# Supply.net
KiCad netlist of a schematic drawn in Altium Designer
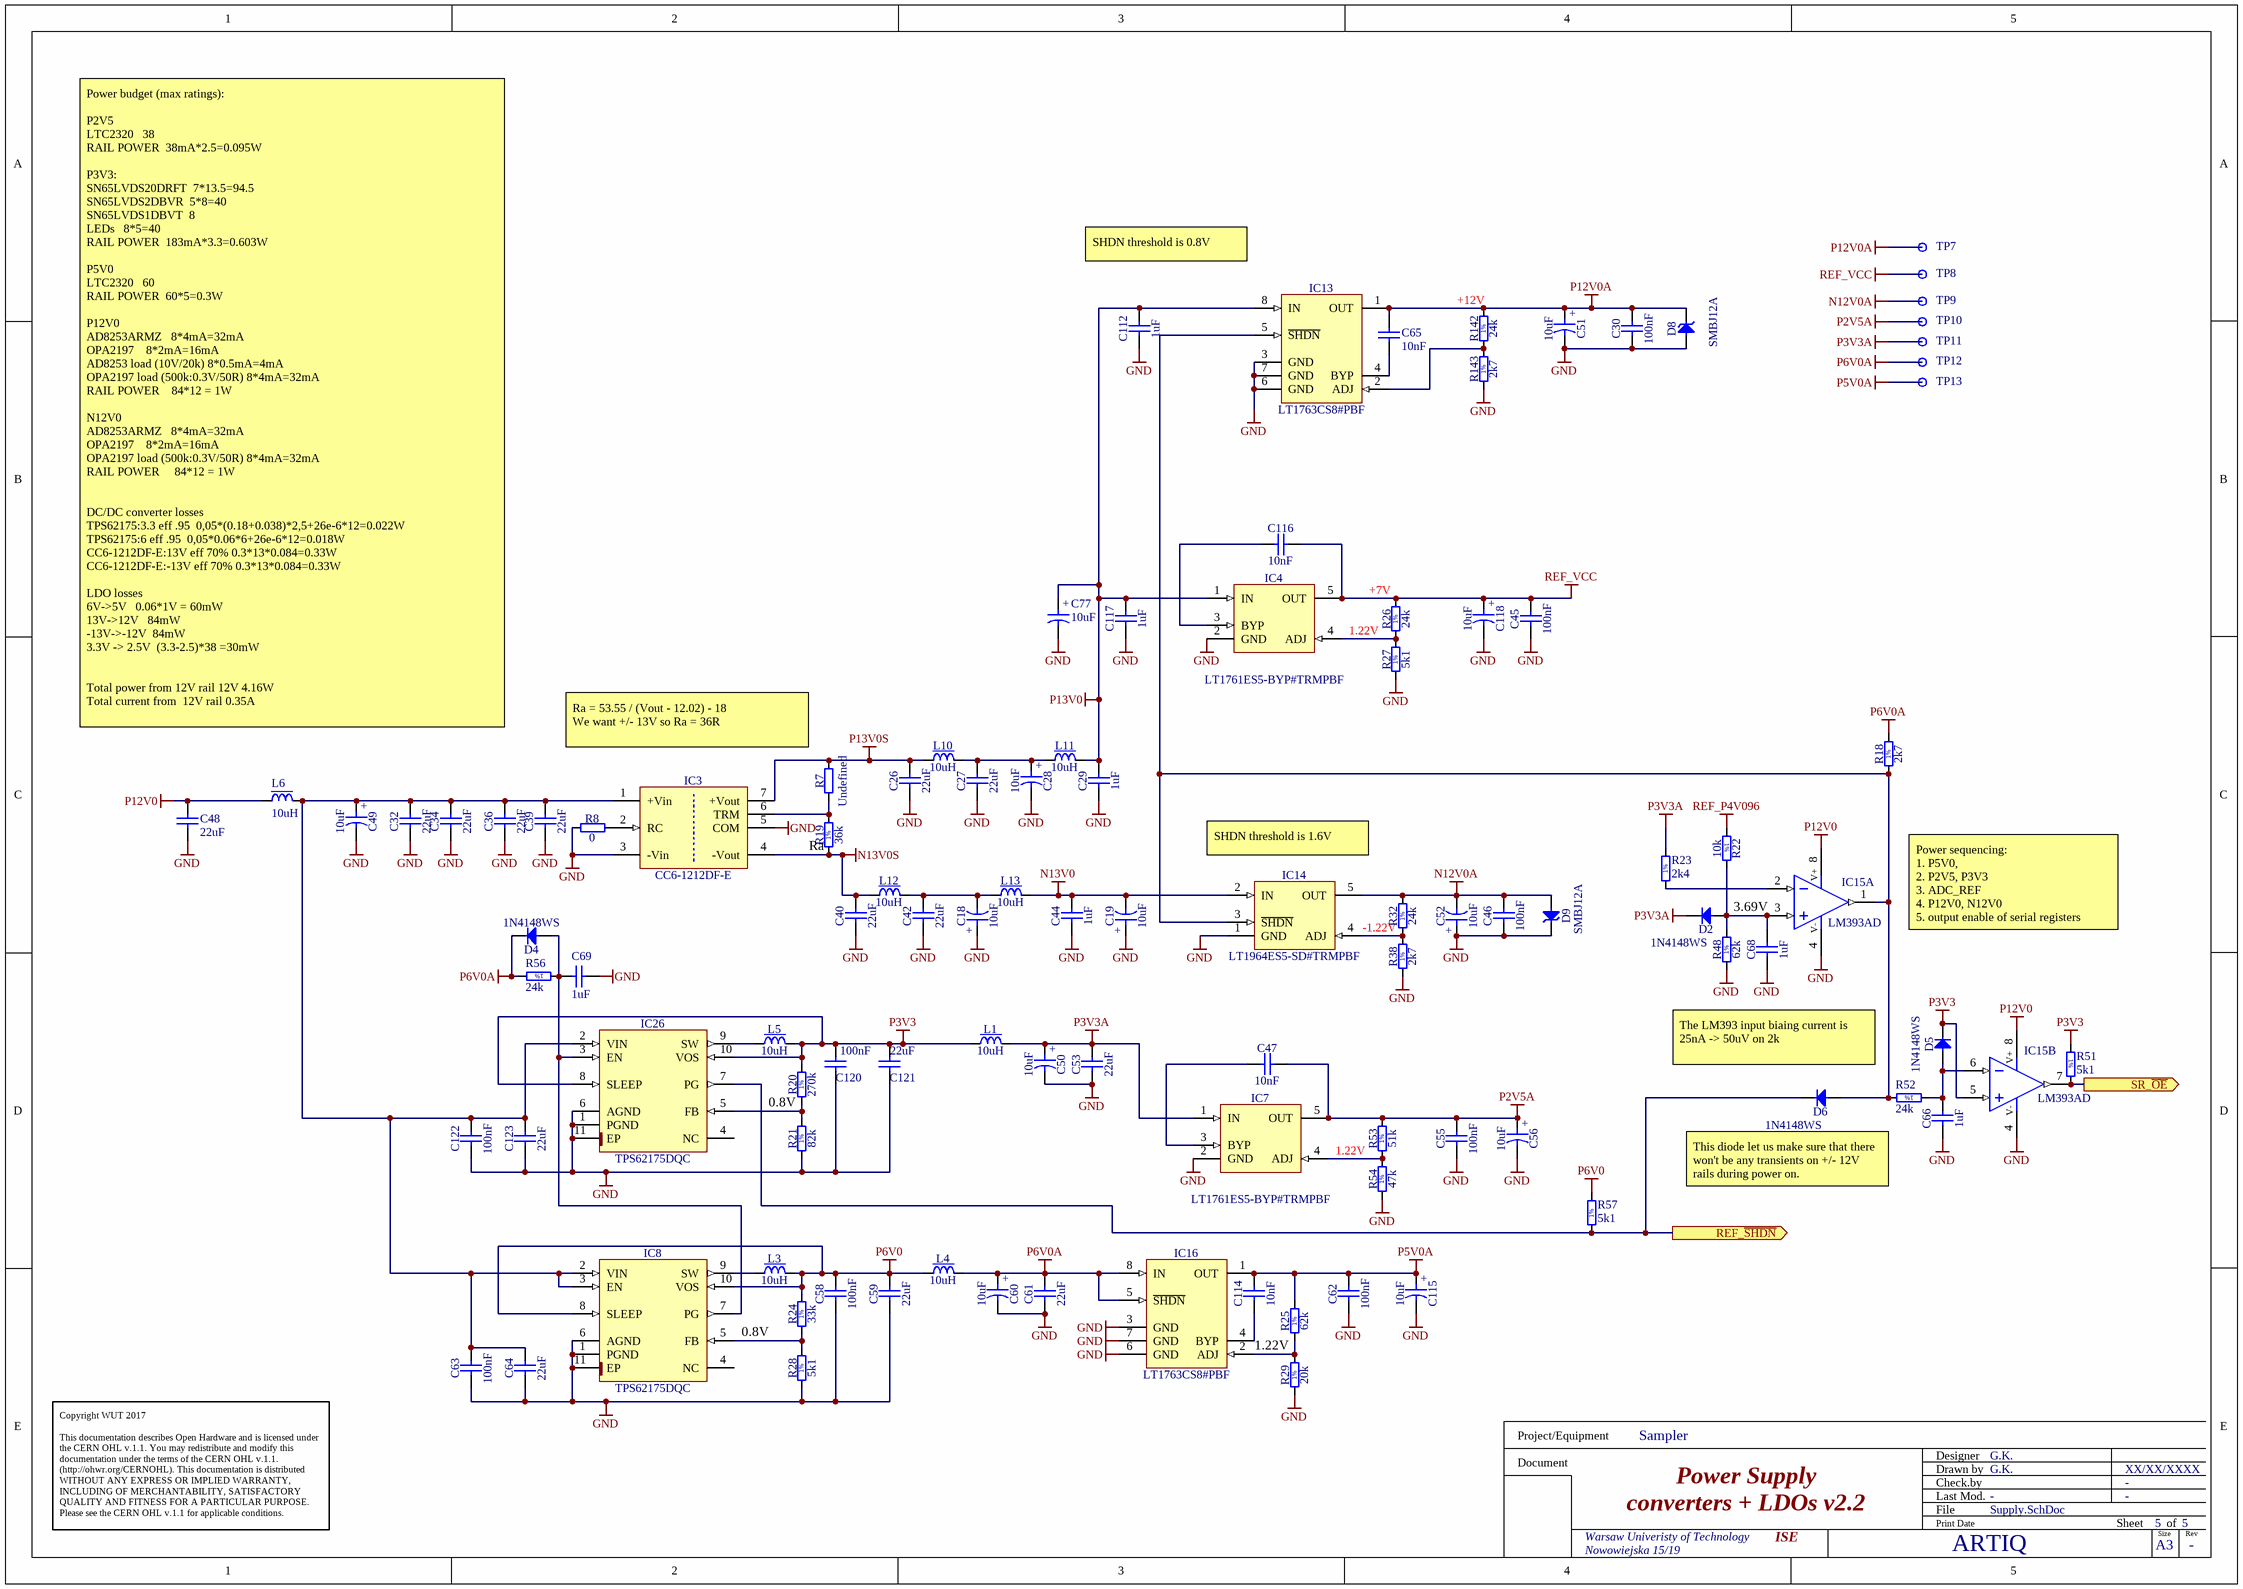
[diagram p0: Supply.SchDoc]

(export (version "E")
  (design (tool "Eeschema 10.0.6"))
  (components
    (comp (ref "C18")
      (value "10uF")
      (footprint "CAPMP3216X180N")
      (description "Polarised capacitor")
      (fields (field (name "PART NUMBER") "CTE3216-18_10UF_16V_20%_AVX_TCJ") (field (name "VOLTAGE") "16V"))
      (libsource (lib "Capacitors") (part "Capacitor - polarized"))
    )
    (comp (ref "C19")
      (value "10uF")
      (footprint "CAPMP3216X180N")
      (description "Polarised capacitor")
      (fields (field (name "PART NUMBER") "CTE3216-18_10UF_16V_20%_AVX_TCJ") (field (name "VOLTAGE") "16V"))
      (libsource (lib "Capacitors") (part "Capacitor - polarized"))
    )
    (comp (ref "C26")
      (value "22uF")
      (footprint "CAPC2012X135N")
      (description "Non-polarised capacitor")
      (fields (field (name "PART NUMBER") "CC0805_22UF_16V_10%_X5R") (field (name "VOLTAGE") "16V"))
      (libsource (lib "Capacitors") (part "Capacitor - non polarized"))
    )
    (comp (ref "C27")
      (value "22uF")
      (footprint "CAPC2012X135N")
      (description "Non-polarised capacitor")
      (fields (field (name "PART NUMBER") "CC0805_22UF_16V_10%_X5R") (field (name "VOLTAGE") "16V"))
      (libsource (lib "Capacitors") (part "Capacitor - non polarized"))
    )
    (comp (ref "C28")
      (value "10uF")
      (footprint "CAPMP3216X180N")
      (description "Polarised capacitor")
      (fields (field (name "PART NUMBER") "CTE3216-18_10UF_16V_20%_AVX_TCJ") (field (name "VOLTAGE") "16V"))
      (libsource (lib "Capacitors") (part "Capacitor - polarized"))
    )
    (comp (ref "C29")
      (value "1uF")
      (footprint "CAPC1608X87N")
      (description "Non-polarised capacitor")
      (fields (field (name "PART NUMBER") "CC0603_1UF_25V_10%_X7R") (field (name "VOLTAGE") "25V"))
      (libsource (lib "Capacitors") (part "Capacitor - non polarized"))
    )
    (comp (ref "C30")
      (value "100nF")
      (footprint "CAPC1005X55N")
      (description "Non-polarised capacitor")
      (fields (field (name "PART NUMBER") "CC0402_100NF_16V_10%_X5R") (field (name "VOLTAGE") "16V"))
      (libsource (lib "Capacitors") (part "Capacitor - non polarized"))
    )
    (comp (ref "C32")
      (value "22uF")
      (footprint "CAPC2012X135N")
      (description "Non-polarised capacitor")
      (fields (field (name "PART NUMBER") "CC0805_22UF_16V_10%_X5R") (field (name "VOLTAGE") "16V"))
      (libsource (lib "Capacitors") (part "Capacitor - non polarized"))
    )
    (comp (ref "C34")
      (value "22uF")
      (footprint "CAPC2012X135N")
      (description "Non-polarised capacitor")
      (fields (field (name "PART NUMBER") "CC0805_22UF_16V_10%_X5R") (field (name "VOLTAGE") "16V"))
      (libsource (lib "Capacitors") (part "Capacitor - non polarized"))
    )
    (comp (ref "C36")
      (value "22uF")
      (footprint "CAPC2012X135N")
      (description "Non-polarised capacitor")
      (fields (field (name "PART NUMBER") "CC0805_22UF_16V_10%_X5R") (field (name "VOLTAGE") "16V"))
      (libsource (lib "Capacitors") (part "Capacitor - non polarized"))
    )
    (comp (ref "C39")
      (value "22uF")
      (footprint "CAPC2012X135N")
      (description "Non-polarised capacitor")
      (fields (field (name "PART NUMBER") "CC0805_22UF_16V_10%_X5R") (field (name "VOLTAGE") "16V"))
      (libsource (lib "Capacitors") (part "Capacitor - non polarized"))
    )
    (comp (ref "C40")
      (value "22uF")
      (footprint "CAPC2012X135N")
      (description "Non-polarised capacitor")
      (fields (field (name "PART NUMBER") "CC0805_22UF_16V_10%_X5R") (field (name "VOLTAGE") "16V"))
      (libsource (lib "Capacitors") (part "Capacitor - non polarized"))
    )
    (comp (ref "C42")
      (value "22uF")
      (footprint "CAPC2012X135N")
      (description "Non-polarised capacitor")
      (fields (field (name "PART NUMBER") "CC0805_22UF_16V_10%_X5R") (field (name "VOLTAGE") "16V"))
      (libsource (lib "Capacitors") (part "Capacitor - non polarized"))
    )
    (comp (ref "C44")
      (value "1uF")
      (footprint "CAPC1608X87N")
      (description "Non-polarised capacitor")
      (fields (field (name "PART NUMBER") "CC0603_1UF_25V_10%_X7R") (field (name "VOLTAGE") "25V"))
      (libsource (lib "Capacitors") (part "Capacitor - non polarized"))
    )
    (comp (ref "C45")
      (value "100nF")
      (footprint "CAPC1005X55N")
      (description "Non-polarised capacitor")
      (fields (field (name "PART NUMBER") "CC0402_100NF_16V_10%_X5R") (field (name "VOLTAGE") "16V"))
      (libsource (lib "Capacitors") (part "Capacitor - non polarized"))
    )
    (comp (ref "C46")
      (value "100nF")
      (footprint "CAPC1005X55N")
      (description "Non-polarised capacitor")
      (fields (field (name "PART NUMBER") "CC0402_100NF_16V_10%_X5R") (field (name "VOLTAGE") "16V"))
      (libsource (lib "Capacitors") (part "Capacitor - non polarized"))
    )
    (comp (ref "C47")
      (value "10nF")
      (footprint "CAPC1608X87N")
      (description "Non-polarised capacitor")
      (fields (field (name "PART NUMBER") "CC0603_10NF_50V_10%_X7R") (field (name "VOLTAGE") "50V"))
      (libsource (lib "Capacitors") (part "Capacitor - non polarized"))
    )
    (comp (ref "C48")
      (value "22uF")
      (footprint "CAPC2012X135N")
      (description "Non-polarised capacitor")
      (fields (field (name "PART NUMBER") "CC0805_22UF_16V_10%_X5R") (field (name "VOLTAGE") "16V"))
      (libsource (lib "Capacitors") (part "Capacitor - non polarized"))
    )
    (comp (ref "C49")
      (value "10uF")
      (footprint "CAPMP3216X180N")
      (description "Polarised capacitor")
      (fields (field (name "PART NUMBER") "CTE3216-18_10UF_16V_20%_AVX_TCJ") (field (name "VOLTAGE") "16V"))
      (libsource (lib "Capacitors") (part "Capacitor - polarized"))
    )
    (comp (ref "C50")
      (value "10uF")
      (footprint "CAPMP3216X180N")
      (description "Polarised capacitor")
      (fields (field (name "PART NUMBER") "CTE3216-18_10UF_16V_20%_AVX_TCJ") (field (name "VOLTAGE") "16V"))
      (libsource (lib "Capacitors") (part "Capacitor - polarized"))
    )
    (comp (ref "C51")
      (value "10uF")
      (footprint "CAPMP3216X180N")
      (description "Polarised capacitor")
      (fields (field (name "PART NUMBER") "CTE3216-18_10UF_16V_20%_AVX_TCJ") (field (name "VOLTAGE") "16V"))
      (libsource (lib "Capacitors") (part "Capacitor - polarized"))
    )
    (comp (ref "C52")
      (value "10uF")
      (footprint "CAPMP3216X180N")
      (description "Polarised capacitor")
      (fields (field (name "PART NUMBER") "CTE3216-18_10UF_16V_20%_AVX_TCJ") (field (name "VOLTAGE") "16V"))
      (libsource (lib "Capacitors") (part "Capacitor - polarized"))
    )
    (comp (ref "C53")
      (value "22uF")
      (footprint "CAPC2012X135N")
      (description "Non-polarised capacitor")
      (fields (field (name "PART NUMBER") "CC0805_22UF_16V_10%_X5R") (field (name "VOLTAGE") "16V"))
      (libsource (lib "Capacitors") (part "Capacitor - non polarized"))
    )
    (comp (ref "C55")
      (value "100nF")
      (footprint "CAPC1005X55N")
      (description "Non-polarised capacitor")
      (fields (field (name "PART NUMBER") "CC0402_100NF_16V_10%_X5R") (field (name "VOLTAGE") "16V"))
      (libsource (lib "Capacitors") (part "Capacitor - non polarized"))
    )
    (comp (ref "C56")
      (value "10uF")
      (footprint "CAPMP3216X180N")
      (description "Polarised capacitor")
      (fields (field (name "PART NUMBER") "CTE3216-18_10UF_16V_20%_AVX_TCJ") (field (name "VOLTAGE") "16V"))
      (libsource (lib "Capacitors") (part "Capacitor - polarized"))
    )
    (comp (ref "C58")
      (value "100nF")
      (footprint "CAPC1005X55N")
      (description "Non-polarised capacitor")
      (fields (field (name "PART NUMBER") "CC0402_100NF_16V_10%_X5R") (field (name "VOLTAGE") "16V"))
      (libsource (lib "Capacitors") (part "Capacitor - non polarized"))
    )
    (comp (ref "C59")
      (value "22uF")
      (footprint "CAPC2012X135N")
      (description "Non-polarised capacitor")
      (fields (field (name "PART NUMBER") "CC0805_22UF_16V_10%_X5R") (field (name "VOLTAGE") "16V"))
      (libsource (lib "Capacitors") (part "Capacitor - non polarized"))
    )
    (comp (ref "C60")
      (value "10uF")
      (footprint "CAPMP3216X180N")
      (description "Polarised capacitor")
      (fields (field (name "PART NUMBER") "CTE3216-18_10UF_16V_20%_AVX_TCJ") (field (name "VOLTAGE") "16V"))
      (libsource (lib "Capacitors") (part "Capacitor - polarized"))
    )
    (comp (ref "C61")
      (value "22uF")
      (footprint "CAPC2012X135N")
      (description "Non-polarised capacitor")
      (fields (field (name "PART NUMBER") "CC0805_22UF_16V_10%_X5R") (field (name "VOLTAGE") "16V"))
      (libsource (lib "Capacitors") (part "Capacitor - non polarized"))
    )
    (comp (ref "C62")
      (value "100nF")
      (footprint "CAPC1005X55N")
      (description "Non-polarised capacitor")
      (fields (field (name "PART NUMBER") "CC0402_100NF_16V_10%_X5R") (field (name "VOLTAGE") "16V"))
      (libsource (lib "Capacitors") (part "Capacitor - non polarized"))
    )
    (comp (ref "C63")
      (value "100nF")
      (footprint "CAPC1005X55N")
      (description "Non-polarised capacitor")
      (fields (field (name "PART NUMBER") "CC0402_100NF_16V_10%_X5R") (field (name "VOLTAGE") "16V"))
      (libsource (lib "Capacitors") (part "Capacitor - non polarized"))
    )
    (comp (ref "C64")
      (value "22uF")
      (footprint "CAPC2012X135N")
      (description "Non-polarised capacitor")
      (fields (field (name "PART NUMBER") "CC0805_22UF_16V_10%_X5R") (field (name "VOLTAGE") "16V"))
      (libsource (lib "Capacitors") (part "Capacitor - non polarized"))
    )
    (comp (ref "C65")
      (value "10nF")
      (footprint "CAPC1608X87N")
      (description "Non-polarised capacitor")
      (fields (field (name "PART NUMBER") "CC0603_10NF_50V_10%_X7R") (field (name "VOLTAGE") "50V"))
      (libsource (lib "Capacitors") (part "Capacitor - non polarized"))
    )
    (comp (ref "C66")
      (value "1uF")
      (footprint "CAPC1608X87N")
      (description "Non-polarised capacitor")
      (fields (field (name "PART NUMBER") "CC0603_1UF_25V_10%_X7R") (field (name "VOLTAGE") "25V"))
      (libsource (lib "Capacitors") (part "Capacitor - non polarized"))
    )
    (comp (ref "C68")
      (value "1uF")
      (footprint "CAPC1608X87N")
      (description "Non-polarised capacitor")
      (fields (field (name "PART NUMBER") "CC0603_1UF_25V_10%_X7R") (field (name "VOLTAGE") "25V"))
      (libsource (lib "Capacitors") (part "Capacitor - non polarized"))
    )
    (comp (ref "C69")
      (value "1uF")
      (footprint "CAPC1608X87N")
      (description "Non-polarised capacitor")
      (fields (field (name "PART NUMBER") "CC0603_1UF_25V_10%_X7R") (field (name "VOLTAGE") "25V"))
      (libsource (lib "Capacitors") (part "Capacitor - non polarized"))
    )
    (comp (ref "C77")
      (value "10uF")
      (footprint "CAPMP3216X180N")
      (description "Polarised capacitor")
      (fields (field (name "PART NUMBER") "CTE3216-18_10UF_16V_20%_AVX_TCJ") (field (name "VOLTAGE") "16V"))
      (libsource (lib "Capacitors") (part "Capacitor - polarized"))
    )
    (comp (ref "C112")
      (value "1uF")
      (footprint "CAPC1608X87N")
      (description "Non-polarised capacitor")
      (fields (field (name "PART NUMBER") "CC0603_1UF_25V_10%_X7R") (field (name "VOLTAGE") "25V"))
      (libsource (lib "Capacitors") (part "Capacitor - non polarized"))
    )
    (comp (ref "C114")
      (value "10nF")
      (footprint "CAPC1608X87N")
      (description "Non-polarised capacitor")
      (fields (field (name "PART NUMBER") "CC0603_10NF_50V_10%_X7R") (field (name "VOLTAGE") "50V"))
      (libsource (lib "Capacitors") (part "Capacitor - non polarized"))
    )
    (comp (ref "C115")
      (value "10uF")
      (footprint "CAPMP3216X180N")
      (description "Polarised capacitor")
      (fields (field (name "PART NUMBER") "CTE3216-18_10UF_16V_20%_AVX_TCJ") (field (name "VOLTAGE") "16V"))
      (libsource (lib "Capacitors") (part "Capacitor - polarized"))
    )
    (comp (ref "C116")
      (value "10nF")
      (footprint "CAPC1608X87N")
      (description "Non-polarised capacitor")
      (fields (field (name "PART NUMBER") "CC0603_10NF_50V_10%_X7R") (field (name "VOLTAGE") "50V"))
      (libsource (lib "Capacitors") (part "Capacitor - non polarized"))
    )
    (comp (ref "C117")
      (value "1uF")
      (footprint "CAPC1608X87N")
      (description "Non-polarised capacitor")
      (fields (field (name "PART NUMBER") "CC0603_1UF_25V_10%_X7R") (field (name "VOLTAGE") "25V"))
      (libsource (lib "Capacitors") (part "Capacitor - non polarized"))
    )
    (comp (ref "C118")
      (value "10uF")
      (footprint "CAPMP3216X180N")
      (description "Polarised capacitor")
      (fields (field (name "PART NUMBER") "CTE3216-18_10UF_16V_20%_AVX_TCJ") (field (name "VOLTAGE") "16V"))
      (libsource (lib "Capacitors") (part "Capacitor - polarized"))
    )
    (comp (ref "C120")
      (value "100nF")
      (footprint "CAPC1005X55N")
      (description "Non-polarised capacitor")
      (fields (field (name "PART NUMBER") "CC0402_100NF_16V_10%_X5R") (field (name "VOLTAGE") "16V"))
      (libsource (lib "Capacitors") (part "Capacitor - non polarized"))
    )
    (comp (ref "C121")
      (value "22uF")
      (footprint "CAPC2012X135N")
      (description "Non-polarised capacitor")
      (fields (field (name "PART NUMBER") "CC0805_22UF_16V_10%_X5R") (field (name "VOLTAGE") "16V"))
      (libsource (lib "Capacitors") (part "Capacitor - non polarized"))
    )
    (comp (ref "C122")
      (value "100nF")
      (footprint "CAPC1005X55N")
      (description "Non-polarised capacitor")
      (fields (field (name "PART NUMBER") "CC0402_100NF_16V_10%_X5R") (field (name "VOLTAGE") "16V"))
      (libsource (lib "Capacitors") (part "Capacitor - non polarized"))
    )
    (comp (ref "C123")
      (value "22uF")
      (footprint "CAPC2012X135N")
      (description "Non-polarised capacitor")
      (fields (field (name "PART NUMBER") "CC0805_22UF_16V_10%_X5R") (field (name "VOLTAGE") "16V"))
      (libsource (lib "Capacitors") (part "Capacitor - non polarized"))
    )
    (comp (ref "D2")
      (value "1N4148WS")
      (footprint "SODFL2512X100N")
      (description "Diode")
      (fields (field (name "VOLTAGE") "75V") (field (name "POWER") "150mA"))
      (libsource (lib "ICs And Semiconductors") (part "Diode"))
    )
    (comp (ref "D4")
      (value "1N4148WS")
      (footprint "SODFL2512X100N")
      (description "Diode")
      (fields (field (name "VOLTAGE") "75V") (field (name "POWER") "150mA"))
      (libsource (lib "ICs And Semiconductors") (part "Diode"))
    )
    (comp (ref "D5")
      (value "1N4148WS")
      (footprint "SODFL2512X100N")
      (description "Diode")
      (fields (field (name "VOLTAGE") "75V") (field (name "POWER") "150mA"))
      (libsource (lib "ICs And Semiconductors") (part "Diode"))
    )
    (comp (ref "D6")
      (value "1N4148WS")
      (footprint "SODFL2512X100N")
      (description "Diode")
      (fields (field (name "VOLTAGE") "75V") (field (name "POWER") "150mA"))
      (libsource (lib "ICs And Semiconductors") (part "Diode"))
    )
    (comp (ref "D8")
      (value "SMBJ12A")
      (footprint "DIOM5336X265N")
      (description "Zener Diode")
      (fields (field (name "VOLTAGE") "12V") (field (name "POWER") "600W"))
      (libsource (lib "ICs And Semiconductors") (part "Diode Zener"))
    )
    (comp (ref "D9")
      (value "SMBJ12A")
      (footprint "DIOM5336X265N")
      (description "Zener Diode")
      (fields (field (name "VOLTAGE") "12V") (field (name "POWER") "600W"))
      (libsource (lib "ICs And Semiconductors") (part "Diode Zener"))
    )
    (comp (ref "IC3")
      (value "CC6-1212DF-E")
      (footprint "CC6-1212DF-E")
      (description "CONV DC/DC 6W DUAL 12V +-12V PCB")
      (fields (field (name "MANUFACTURER") "TDK-Lambda Americas Inc."))
      (libsource (lib "LIBRARY_SCH") (part "DC/DC_CC6-1212DF-E"))
    )
    (comp (ref "IC4")
      (value "LT1761ES5-BYP#TRMPBF")
      (footprint "SOT95P280X100-5N")
      (description "100mA, Low Noise, LDO Micropower Adjustable Regulator in SOT-23")
      (fields (field (name "MANUFACTURER") "LINEAR TECHNOLOGY"))
      (libsource (lib "ICs And Semiconductors") (part "LT1761-BYP"))
    )
    (comp (ref "IC7")
      (value "LT1761ES5-BYP#TRMPBF")
      (footprint "SOT95P280X100-5N")
      (description "100mA, Low Noise, LDO Micropower Adjustable Regulator in SOT-23")
      (fields (field (name "MANUFACTURER") "LINEAR TECHNOLOGY"))
      (libsource (lib "ICs And Semiconductors") (part "LT1761-BYP"))
    )
    (comp (ref "IC8")
      (value "TPS62175DQC")
      (footprint "SON50P200X300X80-11N-R94X250")
      (description "4.75-28VDC to 1-6VDC, 500mA Step-Down Converter With Sleep Mode")
      (fields (field (name "MANUFACTURER") "TEXAS INSTRUMENTS"))
      (libsource (lib "ICs And Semiconductors") (part "TPS62175"))
    )
    (comp (ref "IC13")
      (value "LT1763CS8#PBF")
      (footprint "SOIC127P600X175-8N")
      (description "1.22V to 20V 500mA, Low Noise, LDO Adjustable Micropower Regulator")
      (fields (field (name "MANUFACTURER") "LINEAR TECHNOLOGY"))
      (libsource (lib "ICs And Semiconductors") (part "LT1763xS8"))
    )
    (comp (ref "IC14")
      (value "LT1964ES5-SD#TRMPBF")
      (footprint "SOT95P280X100-5N")
      (description "200mA, Low Noise, Low Dropout Negative Micropower Regulator")
      (fields (field (name "MANUFACTURER") "LINEAR TECHNOLOGY"))
      (libsource (lib "ICs And Semiconductors") (part "LT1964-SD"))
    )
    (comp (ref "IC15")
      (value "LM393AD")
      (footprint "SOIC127P600X175-8N")
      (description "Dual Operational Amplifier")
      (fields (field (name "MANUFACTURER") "TEXAS INSTRUMENTS"))
      (libsource (lib "ICs And Semiconductors") (part "Operational Amplifier x2 Type1"))
    )
    (comp (ref "IC16")
      (value "LT1763CS8#PBF")
      (footprint "SOIC127P600X175-8N")
      (description "1.22V to 20V 500mA, Low Noise, LDO Adjustable Micropower Regulator")
      (fields (field (name "MANUFACTURER") "LINEAR TECHNOLOGY"))
      (libsource (lib "ICs And Semiconductors") (part "LT1763xS8"))
    )
    (comp (ref "IC26")
      (value "TPS62175DQC")
      (footprint "SON50P200X300X80-11N-R94X250")
      (description "4.75-28VDC to 1-6VDC, 500mA Step-Down Converter With Sleep Mode")
      (fields (field (name "MANUFACTURER") "TEXAS INSTRUMENTS"))
      (libsource (lib "ICs And Semiconductors") (part "TPS62175"))
    )
    (comp (ref "L1")
      (value "10uH")
      (footprint "IND_MURATA-PS_8400")
      (description "Inductor With Core")
      (fields (field (name "PART NUMBER") "IND_10UH_10%_MURATA-PS_8400") (field (name "POWER") "950mA"))
      (libsource (lib "Inductors & Transformers") (part "Inductor With Magnetic core"))
    )
    (comp (ref "L3")
      (value "10uH")
      (footprint "IND_MURATA-PS_8400")
      (description "Inductor With Core")
      (fields (field (name "PART NUMBER") "IND_10UH_10%_MURATA-PS_8400") (field (name "POWER") "950mA"))
      (libsource (lib "Inductors & Transformers") (part "Inductor With Magnetic core"))
    )
    (comp (ref "L4")
      (value "10uH")
      (footprint "IND_MURATA-PS_8400")
      (description "Inductor With Core")
      (fields (field (name "PART NUMBER") "IND_10UH_10%_MURATA-PS_8400") (field (name "POWER") "950mA"))
      (libsource (lib "Inductors & Transformers") (part "Inductor With Magnetic core"))
    )
    (comp (ref "L5")
      (value "10uH")
      (footprint "IND_MURATA-PS_8400")
      (description "Inductor With Core")
      (fields (field (name "PART NUMBER") "IND_10UH_10%_MURATA-PS_8400") (field (name "POWER") "950mA"))
      (libsource (lib "Inductors & Transformers") (part "Inductor With Magnetic core"))
    )
    (comp (ref "L6")
      (value "10uH")
      (footprint "IND_MURATA-PS_8400")
      (description "Inductor With Core")
      (fields (field (name "PART NUMBER") "IND_10UH_10%_MURATA-PS_8400") (field (name "POWER") "950mA"))
      (libsource (lib "Inductors & Transformers") (part "Inductor With Magnetic core"))
    )
    (comp (ref "L10")
      (value "10uH")
      (footprint "IND_MURATA-PS_8400")
      (description "Inductor With Core")
      (fields (field (name "PART NUMBER") "IND_10UH_10%_MURATA-PS_8400") (field (name "POWER") "950mA"))
      (libsource (lib "Inductors & Transformers") (part "Inductor With Magnetic core"))
    )
    (comp (ref "L11")
      (value "10uH")
      (footprint "IND_MURATA-PS_8400")
      (description "Inductor With Core")
      (fields (field (name "PART NUMBER") "IND_10UH_10%_MURATA-PS_8400") (field (name "POWER") "950mA"))
      (libsource (lib "Inductors & Transformers") (part "Inductor With Magnetic core"))
    )
    (comp (ref "L12")
      (value "10uH")
      (footprint "IND_MURATA-PS_8400")
      (description "Inductor With Core")
      (fields (field (name "PART NUMBER") "IND_10UH_10%_MURATA-PS_8400") (field (name "POWER") "950mA"))
      (libsource (lib "Inductors & Transformers") (part "Inductor With Magnetic core"))
    )
    (comp (ref "L13")
      (value "10uH")
      (footprint "IND_MURATA-PS_8400")
      (description "Inductor With Core")
      (fields (field (name "PART NUMBER") "IND_10UH_10%_MURATA-PS_8400") (field (name "POWER") "950mA"))
      (libsource (lib "Inductors & Transformers") (part "Inductor With Magnetic core"))
    )
    (comp (ref "R7")
      (value "Undefined")
      (footprint "RESC1608X55N")
      (description "Resistor")
      (fields (field (name "PART NUMBER") "R0603_NO-VALUE"))
      (libsource (lib "Resistors") (part "Resistor"))
    )
    (comp (ref "R8")
      (value "0")
      (footprint "RESC1005X40N")
      (description "Resistor")
      (fields (field (name "PART NUMBER") "R0402_0R_JUMPER") (field (name "MANUFACTURER") "GENERIC"))
      (libsource (lib "Resistors") (part "Resistor"))
    )
    (comp (ref "R18")
      (value "2k7")
      (footprint "RESC1608X55N")
      (description "Resistor - 1%")
      (fields (field (name "PART NUMBER") "R0603_2K7_1%_0.1W_100PPM") (field (name "POWER") "0.1W"))
      (libsource (lib "Resistors") (part "Resistor - 1%"))
    )
    (comp (ref "R19")
      (value "36k")
      (footprint "RESC1608X55N")
      (description "Resistor - 1%")
      (fields (field (name "PART NUMBER") "R0603_36K_1%_0.1W_100PPM") (field (name "POWER") "0.1W"))
      (libsource (lib "Resistors") (part "Resistor - 1%"))
    )
    (comp (ref "R20")
      (value "270k")
      (footprint "RESC1608X55N")
      (description "Resistor - 1%")
      (fields (field (name "PART NUMBER") "R0603_270K_1%_0.1W_100PPM") (field (name "POWER") "0.1W"))
      (libsource (lib "Resistors") (part "Resistor - 1%"))
    )
    (comp (ref "R21")
      (value "82k")
      (footprint "RESC1608X55N")
      (description "Resistor - 1%")
      (fields (field (name "PART NUMBER") "R0603_82K_1%_0.1W_100PPM") (field (name "POWER") "0.1W"))
      (libsource (lib "Resistors") (part "Resistor - 1%"))
    )
    (comp (ref "R22")
      (value "10k")
      (footprint "RESC1005X40N")
      (description "Resistor - 1%")
      (fields (field (name "PART NUMBER") "R0402_10K_1%_0.0625W_100PPM") (field (name "POWER") "0.0625W"))
      (libsource (lib "Resistors") (part "Resistor - 1%"))
    )
    (comp (ref "R23")
      (value "2k4")
      (footprint "RESC1005X40N")
      (description "Resistor - 1%")
      (fields (field (name "PART NUMBER") "R0402_2K4_1%_0.0625W_100PPM") (field (name "POWER") "0.0625W"))
      (libsource (lib "Resistors") (part "Resistor - 1%"))
    )
    (comp (ref "R24")
      (value "33k")
      (footprint "RESC1005X40N")
      (description "Resistor - 1%")
      (fields (field (name "PART NUMBER") "R0402_33K_1%_0.0625W_100PPM") (field (name "POWER") "0.0625W"))
      (libsource (lib "Resistors") (part "Resistor - 1%"))
    )
    (comp (ref "R25")
      (value "62k")
      (footprint "RESC1005X40N")
      (description "Resistor - 1%")
      (fields (field (name "PART NUMBER") "R0402_62K_1%_0.0625W_100PPM") (field (name "POWER") "0.0625W"))
      (libsource (lib "Resistors") (part "Resistor - 1%"))
    )
    (comp (ref "R26")
      (value "24k")
      (footprint "RESC1608X55N")
      (description "Resistor - 1%")
      (fields (field (name "PART NUMBER") "R0603_24K_1%_0.1W_100PPM") (field (name "POWER") "0.1W"))
      (libsource (lib "Resistors") (part "Resistor - 1%"))
    )
    (comp (ref "R27")
      (value "5k1")
      (footprint "RESC1005X40N")
      (description "Resistor - 1%")
      (fields (field (name "PART NUMBER") "R0402_5K1_1%_0.0625W_100PPM") (field (name "POWER") "0.0625W"))
      (libsource (lib "Resistors") (part "Resistor - 1%"))
    )
    (comp (ref "R28")
      (value "5k1")
      (footprint "RESC1005X40N")
      (description "Resistor - 1%")
      (fields (field (name "PART NUMBER") "R0402_5K1_1%_0.0625W_100PPM") (field (name "POWER") "0.0625W"))
      (libsource (lib "Resistors") (part "Resistor - 1%"))
    )
    (comp (ref "R29")
      (value "20k")
      (footprint "RESC1005X40N")
      (description "Resistor - 1%")
      (fields (field (name "PART NUMBER") "R0402_20K_1%_0.0625W_100PPM") (field (name "POWER") "0.0625W"))
      (libsource (lib "Resistors") (part "Resistor - 1%"))
    )
    (comp (ref "R32")
      (value "24k")
      (footprint "RESC1608X55N")
      (description "Resistor - 1%")
      (fields (field (name "PART NUMBER") "R0603_24K_1%_0.1W_100PPM") (field (name "POWER") "0.1W"))
      (libsource (lib "Resistors") (part "Resistor - 1%"))
    )
    (comp (ref "R38")
      (value "2k7")
      (footprint "RESC1608X55N")
      (description "Resistor - 1%")
      (fields (field (name "PART NUMBER") "R0603_2K7_1%_0.1W_100PPM") (field (name "POWER") "0.1W"))
      (libsource (lib "Resistors") (part "Resistor - 1%"))
    )
    (comp (ref "R48")
      (value "62k")
      (footprint "RESC1005X40N")
      (description "Resistor - 1%")
      (fields (field (name "PART NUMBER") "R0402_62K_1%_0.0625W_100PPM") (field (name "POWER") "0.0625W"))
      (libsource (lib "Resistors") (part "Resistor - 1%"))
    )
    (comp (ref "R51")
      (value "5k1")
      (footprint "RESC1005X40N")
      (description "Resistor - 1%")
      (fields (field (name "PART NUMBER") "R0402_5K1_1%_0.0625W_100PPM") (field (name "POWER") "0.0625W"))
      (libsource (lib "Resistors") (part "Resistor - 1%"))
    )
    (comp (ref "R52")
      (value "24k")
      (footprint "RESC1608X55N")
      (description "Resistor - 1%")
      (fields (field (name "PART NUMBER") "R0603_24K_1%_0.1W_100PPM") (field (name "POWER") "0.1W"))
      (libsource (lib "Resistors") (part "Resistor - 1%"))
    )
    (comp (ref "R53")
      (value "51k")
      (footprint "RESC1005X40N")
      (description "Resistor - 1%")
      (fields (field (name "PART NUMBER") "R0402_51K_1%_0.0625W_100PPM") (field (name "POWER") "0.0625W"))
      (libsource (lib "Resistors") (part "Resistor - 1%"))
    )
    (comp (ref "R54")
      (value "47k")
      (footprint "RESC1005X40N")
      (description "Resistor - 1%")
      (fields (field (name "PART NUMBER") "R0402_47K_1%_0.0625W_100PPM") (field (name "POWER") "0.0625W"))
      (libsource (lib "Resistors") (part "Resistor - 1%"))
    )
    (comp (ref "R56")
      (value "24k")
      (footprint "RESC1608X55N")
      (description "Resistor - 1%")
      (fields (field (name "PART NUMBER") "R0603_24K_1%_0.1W_100PPM") (field (name "POWER") "0.1W"))
      (libsource (lib "Resistors") (part "Resistor - 1%"))
    )
    (comp (ref "R57")
      (value "5k1")
      (footprint "RESC1005X40N")
      (description "Resistor - 1%")
      (fields (field (name "PART NUMBER") "R0402_5K1_1%_0.0625W_100PPM") (field (name "POWER") "0.0625W"))
      (libsource (lib "Resistors") (part "Resistor - 1%"))
    )
    (comp (ref "R142")
      (value "24k")
      (footprint "RESC1608X55N")
      (description "Resistor - 1%")
      (fields (field (name "PART NUMBER") "R0603_24K_1%_0.1W_100PPM") (field (name "POWER") "0.1W"))
      (libsource (lib "Resistors") (part "Resistor - 1%"))
    )
    (comp (ref "R143")
      (value "2k7")
      (footprint "RESC1608X55N")
      (description "Resistor - 1%")
      (fields (field (name "PART NUMBER") "R0603_2K7_1%_0.1W_100PPM") (field (name "POWER") "0.1W"))
      (libsource (lib "Resistors") (part "Resistor - 1%"))
    )
    (comp (ref "TP7")
      (value "Test Point")
      (footprint "TPS127")
      (fields (field (name "PART NUMBER") "SMD_PAD_1.27X1.27MM"))
      (libsource (lib "Eletro-mechanical") (part "Test Point"))
    )
    (comp (ref "TP8")
      (value "Test Point")
      (footprint "TPS127")
      (fields (field (name "PART NUMBER") "SMD_PAD_1.27X1.27MM"))
      (libsource (lib "Eletro-mechanical") (part "Test Point"))
    )
    (comp (ref "TP9")
      (value "Test Point")
      (footprint "TPS127")
      (fields (field (name "PART NUMBER") "SMD_PAD_1.27X1.27MM"))
      (libsource (lib "Eletro-mechanical") (part "Test Point"))
    )
    (comp (ref "TP10")
      (value "Test Point")
      (footprint "TPS127")
      (fields (field (name "PART NUMBER") "SMD_PAD_1.27X1.27MM"))
      (libsource (lib "Eletro-mechanical") (part "Test Point"))
    )
    (comp (ref "TP11")
      (value "Test Point")
      (footprint "TPS127")
      (fields (field (name "PART NUMBER") "SMD_PAD_1.27X1.27MM"))
      (libsource (lib "Eletro-mechanical") (part "Test Point"))
    )
    (comp (ref "TP12")
      (value "Test Point")
      (footprint "TPS127")
      (fields (field (name "PART NUMBER") "SMD_PAD_1.27X1.27MM"))
      (libsource (lib "Eletro-mechanical") (part "Test Point"))
    )
    (comp (ref "TP13")
      (value "Test Point")
      (footprint "TPS127")
      (fields (field (name "PART NUMBER") "SMD_PAD_1.27X1.27MM"))
      (libsource (lib "Eletro-mechanical") (part "Test Point"))
    )
  )
  (nets
    (net (code "1") (name "/REF_~{SHDN}") (class "Default")
      (node (ref "D6") (pin "1") (pinfunction "C_1") (pintype "passive"))
      (node (ref "IC26") (pin "7") (pinfunction "PG_7") (pintype "output"))
      (node (ref "R57") (pin "1") (pinfunction "1_1") (pintype "passive"))
    )
    (net (code "2") (name "/SR_~{OE}") (class "Default")
      (node (ref "IC15") (pin "7") (pinfunction "OUT_7") (pintype "output"))
      (node (ref "R51") (pin "2") (pinfunction "2_2") (pintype "passive"))
    )
    (net (code "3") (name "GND") (class "Default")
      (node (ref "C112") (pin "1") (pinfunction "1_1") (pintype "passive"))
      (node (ref "C115") (pin "2") (pinfunction "2_2") (pintype "passive"))
      (node (ref "C117") (pin "1") (pinfunction "1_1") (pintype "passive"))
      (node (ref "C118") (pin "2") (pinfunction "2_2") (pintype "passive"))
      (node (ref "C120") (pin "1") (pinfunction "1_1") (pintype "passive"))
      (node (ref "C121") (pin "1") (pinfunction "1_1") (pintype "passive"))
      (node (ref "C122") (pin "1") (pinfunction "1_1") (pintype "passive"))
      (node (ref "C123") (pin "1") (pinfunction "1_1") (pintype "passive"))
      (node (ref "C18") (pin "1") (pinfunction "1_1") (pintype "passive"))
      (node (ref "C19") (pin "1") (pinfunction "1_1") (pintype "passive"))
      (node (ref "C26") (pin "1") (pinfunction "1_1") (pintype "passive"))
      (node (ref "C27") (pin "1") (pinfunction "1_1") (pintype "passive"))
      (node (ref "C28") (pin "2") (pinfunction "2_2") (pintype "passive"))
      (node (ref "C29") (pin "1") (pinfunction "1_1") (pintype "passive"))
      (node (ref "C30") (pin "1") (pinfunction "1_1") (pintype "passive"))
      (node (ref "C32") (pin "1") (pinfunction "1_1") (pintype "passive"))
      (node (ref "C34") (pin "1") (pinfunction "1_1") (pintype "passive"))
      (node (ref "C36") (pin "1") (pinfunction "1_1") (pintype "passive"))
      (node (ref "C39") (pin "1") (pinfunction "1_1") (pintype "passive"))
      (node (ref "C40") (pin "1") (pinfunction "1_1") (pintype "passive"))
      (node (ref "C42") (pin "1") (pinfunction "1_1") (pintype "passive"))
      (node (ref "C44") (pin "1") (pinfunction "1_1") (pintype "passive"))
      (node (ref "C45") (pin "1") (pinfunction "1_1") (pintype "passive"))
      (node (ref "C46") (pin "1") (pinfunction "1_1") (pintype "passive"))
      (node (ref "C48") (pin "1") (pinfunction "1_1") (pintype "passive"))
      (node (ref "C49") (pin "2") (pinfunction "2_2") (pintype "passive"))
      (node (ref "C50") (pin "2") (pinfunction "2_2") (pintype "passive"))
      (node (ref "C51") (pin "2") (pinfunction "2_2") (pintype "passive"))
      (node (ref "C52") (pin "1") (pinfunction "1_1") (pintype "passive"))
      (node (ref "C53") (pin "1") (pinfunction "1_1") (pintype "passive"))
      (node (ref "C55") (pin "1") (pinfunction "1_1") (pintype "passive"))
      (node (ref "C56") (pin "2") (pinfunction "2_2") (pintype "passive"))
      (node (ref "C58") (pin "1") (pinfunction "1_1") (pintype "passive"))
      (node (ref "C59") (pin "1") (pinfunction "1_1") (pintype "passive"))
      (node (ref "C60") (pin "2") (pinfunction "2_2") (pintype "passive"))
      (node (ref "C61") (pin "1") (pinfunction "1_1") (pintype "passive"))
      (node (ref "C62") (pin "1") (pinfunction "1_1") (pintype "passive"))
      (node (ref "C63") (pin "1") (pinfunction "1_1") (pintype "passive"))
      (node (ref "C64") (pin "1") (pinfunction "1_1") (pintype "passive"))
      (node (ref "C66") (pin "1") (pinfunction "1_1") (pintype "passive"))
      (node (ref "C68") (pin "1") (pinfunction "1_1") (pintype "passive"))
      (node (ref "C69") (pin "1") (pinfunction "1_1") (pintype "passive"))
      (node (ref "C77") (pin "2") (pinfunction "2_2") (pintype "passive"))
      (node (ref "D8") (pin "2") (pinfunction "A_2") (pintype "passive"))
      (node (ref "D9") (pin "1") (pinfunction "C_1") (pintype "passive"))
      (node (ref "IC13") (pin "3") (pinfunction "GND_3") (pintype "power_in"))
      (node (ref "IC13") (pin "6") (pinfunction "GND_6") (pintype "power_in"))
      (node (ref "IC13") (pin "7") (pinfunction "GND_7") (pintype "power_in"))
      (node (ref "IC14") (pin "1") (pinfunction "GND_1") (pintype "power_in"))
      (node (ref "IC15") (pin "4") (pinfunction "V-_4") (pintype "power_in"))
      (node (ref "IC16") (pin "3") (pinfunction "GND_3") (pintype "power_in"))
      (node (ref "IC16") (pin "6") (pinfunction "GND_6") (pintype "power_in"))
      (node (ref "IC16") (pin "7") (pinfunction "GND_7") (pintype "power_in"))
      (node (ref "IC26") (pin "1") (pinfunction "PGND_1") (pintype "power_in"))
      (node (ref "IC26") (pin "11") (pinfunction "EP_11") (pintype "power_in"))
      (node (ref "IC26") (pin "6") (pinfunction "AGND_6") (pintype "power_in"))
      (node (ref "IC3") (pin "3") (pinfunction "-Vin_3") (pintype "power_in"))
      (node (ref "IC3") (pin "5") (pinfunction "COM_5") (pintype "power_in"))
      (node (ref "IC4") (pin "2") (pinfunction "GND_2") (pintype "power_in"))
      (node (ref "IC7") (pin "2") (pinfunction "GND_2") (pintype "power_in"))
      (node (ref "IC8") (pin "1") (pinfunction "PGND_1") (pintype "power_in"))
      (node (ref "IC8") (pin "11") (pinfunction "EP_11") (pintype "power_in"))
      (node (ref "IC8") (pin "6") (pinfunction "AGND_6") (pintype "power_in"))
      (node (ref "R143") (pin "1") (pinfunction "1_1") (pintype "passive"))
      (node (ref "R21") (pin "1") (pinfunction "1_1") (pintype "passive"))
      (node (ref "R27") (pin "1") (pinfunction "1_1") (pintype "passive"))
      (node (ref "R28") (pin "1") (pinfunction "1_1") (pintype "passive"))
      (node (ref "R29") (pin "1") (pinfunction "1_1") (pintype "passive"))
      (node (ref "R38") (pin "1") (pinfunction "1_1") (pintype "passive"))
      (node (ref "R48") (pin "1") (pinfunction "1_1") (pintype "passive"))
      (node (ref "R54") (pin "1") (pinfunction "1_1") (pintype "passive"))
      (node (ref "R8") (pin "1") (pinfunction "1_1") (pintype "passive"))
    )
    (net (code "4") (name "N12V0A") (class "Default")
      (node (ref "C46") (pin "2") (pinfunction "2_2") (pintype "passive"))
      (node (ref "C52") (pin "2") (pinfunction "2_2") (pintype "passive"))
      (node (ref "D9") (pin "2") (pinfunction "A_2") (pintype "passive"))
      (node (ref "IC14") (pin "5") (pinfunction "OUT_5") (pintype "power_in"))
      (node (ref "R32") (pin "2") (pinfunction "2_2") (pintype "passive"))
      (node (ref "TP9") (pin "1") (pinfunction "1_1") (pintype "bidirectional"))
    )
    (net (code "5") (name "N13V0") (class "Default")
      (node (ref "C19") (pin "2") (pinfunction "2_2") (pintype "passive"))
      (node (ref "C44") (pin "2") (pinfunction "2_2") (pintype "passive"))
      (node (ref "IC14") (pin "2") (pinfunction "IN_2") (pintype "input"))
      (node (ref "L13") (pin "2") (pinfunction "2_2") (pintype "passive"))
    )
    (net (code "6") (name "N13V0S") (class "Default")
      (node (ref "C40") (pin "2") (pinfunction "2_2") (pintype "passive"))
      (node (ref "IC3") (pin "4") (pinfunction "-Vout_4") (pintype "power_in"))
      (node (ref "L12") (pin "1") (pinfunction "1_1") (pintype "passive"))
      (node (ref "R19") (pin "1") (pinfunction "1_1") (pintype "passive"))
    )
    (net (code "7") (name "Net-(C18-Pad2)") (class "Default")
      (node (ref "C18") (pin "2") (pinfunction "2_2") (pintype "passive"))
      (node (ref "C42") (pin "2") (pinfunction "2_2") (pintype "passive"))
      (node (ref "L12") (pin "2") (pinfunction "2_2") (pintype "passive"))
      (node (ref "L13") (pin "1") (pinfunction "1_1") (pintype "passive"))
    )
    (net (code "8") (name "Net-(C27-Pad2)") (class "Default")
      (node (ref "C27") (pin "2") (pinfunction "2_2") (pintype "passive"))
      (node (ref "C28") (pin "1") (pinfunction "1_1") (pintype "passive"))
      (node (ref "L10") (pin "2") (pinfunction "2_2") (pintype "passive"))
      (node (ref "L11") (pin "1") (pinfunction "1_1") (pintype "passive"))
    )
    (net (code "9") (name "Net-(D2-A)") (class "Default")
      (node (ref "C68") (pin "2") (pinfunction "2_2") (pintype "passive"))
      (node (ref "D2") (pin "2") (pinfunction "A_2") (pintype "passive"))
      (node (ref "IC15") (pin "3") (pinfunction "IN+_3") (pintype "input"))
      (node (ref "R22") (pin "2") (pinfunction "2_2") (pintype "passive"))
      (node (ref "R48") (pin "2") (pinfunction "2_2") (pintype "passive"))
    )
    (net (code "10") (name "Net-(D4-A)") (class "Default")
      (node (ref "C69") (pin "2") (pinfunction "2_2") (pintype "passive"))
      (node (ref "D4") (pin "2") (pinfunction "A_2") (pintype "passive"))
      (node (ref "IC26") (pin "3") (pinfunction "EN_3") (pintype "input"))
      (node (ref "IC8") (pin "7") (pinfunction "PG_7") (pintype "output"))
      (node (ref "R56") (pin "1") (pinfunction "1_1") (pintype "passive"))
    )
    (net (code "11") (name "Net-(D5-A)") (class "Default")
      (node (ref "C66") (pin "2") (pinfunction "2_2") (pintype "passive"))
      (node (ref "D5") (pin "2") (pinfunction "A_2") (pintype "passive"))
      (node (ref "IC15") (pin "6") (pinfunction "IN-_6") (pintype "input"))
      (node (ref "R52") (pin "1") (pinfunction "1_1") (pintype "passive"))
    )
    (net (code "12") (name "Net-(D6-A)") (class "Default")
      (node (ref "D6") (pin "2") (pinfunction "A_2") (pintype "passive"))
      (node (ref "IC13") (pin "5") (pinfunction "~{SHDN}_5") (pintype "input"))
      (node (ref "IC14") (pin "3") (pinfunction "~{SHDN}_3") (pintype "input"))
      (node (ref "IC15") (pin "1") (pinfunction "OUT_1") (pintype "output"))
      (node (ref "R18") (pin "1") (pinfunction "1_1") (pintype "passive"))
      (node (ref "R52") (pin "2") (pinfunction "2_2") (pintype "passive"))
    )
    (net (code "13") (name "Net-(IC3-RC)") (class "Default")
      (node (ref "IC3") (pin "2") (pinfunction "RC_2") (pintype "input"))
      (node (ref "R8") (pin "2") (pinfunction "2_2") (pintype "passive"))
    )
    (net (code "14") (name "Net-(IC3-TRM)") (class "Default")
      (node (ref "IC3") (pin "6") (pinfunction "TRM_6") (pintype "power_in"))
      (node (ref "R19") (pin "2") (pinfunction "2_2") (pintype "passive"))
      (node (ref "R7") (pin "1") (pinfunction "1_1") (pintype "passive"))
    )
    (net (code "15") (name "Net-(IC4-ADJ)") (class "Default")
      (node (ref "IC4") (pin "4") (pinfunction "ADJ_4") (pintype "input"))
      (node (ref "R26") (pin "1") (pinfunction "1_1") (pintype "passive"))
      (node (ref "R27") (pin "2") (pinfunction "2_2") (pintype "passive"))
    )
    (net (code "16") (name "Net-(IC4-BYP)") (class "Default")
      (node (ref "C116") (pin "1") (pinfunction "1_1") (pintype "passive"))
      (node (ref "IC4") (pin "3") (pinfunction "BYP_3") (pintype "input"))
    )
    (net (code "17") (name "Net-(IC7-ADJ)") (class "Default")
      (node (ref "IC7") (pin "4") (pinfunction "ADJ_4") (pintype "input"))
      (node (ref "R53") (pin "1") (pinfunction "1_1") (pintype "passive"))
      (node (ref "R54") (pin "2") (pinfunction "2_2") (pintype "passive"))
    )
    (net (code "18") (name "Net-(IC7-BYP)") (class "Default")
      (node (ref "C47") (pin "1") (pinfunction "1_1") (pintype "passive"))
      (node (ref "IC7") (pin "3") (pinfunction "BYP_3") (pintype "input"))
    )
    (net (code "19") (name "Net-(IC8-FB)") (class "Default")
      (node (ref "IC8") (pin "5") (pinfunction "FB_5") (pintype "input"))
      (node (ref "R24") (pin "1") (pinfunction "1_1") (pintype "passive"))
      (node (ref "R28") (pin "2") (pinfunction "2_2") (pintype "passive"))
    )
    (net (code "20") (name "Net-(IC8-SW)") (class "Default")
      (node (ref "IC8") (pin "9") (pinfunction "SW_9") (pintype "output"))
      (node (ref "L3") (pin "1") (pinfunction "1_1") (pintype "passive"))
    )
    (net (code "21") (name "Net-(IC13-ADJ)") (class "Default")
      (node (ref "IC13") (pin "2") (pinfunction "ADJ_2") (pintype "input"))
      (node (ref "R142") (pin "1") (pinfunction "1_1") (pintype "passive"))
      (node (ref "R143") (pin "2") (pinfunction "2_2") (pintype "passive"))
    )
    (net (code "22") (name "Net-(IC13-BYP)") (class "Default")
      (node (ref "C65") (pin "1") (pinfunction "1_1") (pintype "passive"))
      (node (ref "IC13") (pin "4") (pinfunction "BYP_4") (pintype "passive"))
    )
    (net (code "23") (name "Net-(IC14-ADJ)") (class "Default")
      (node (ref "IC14") (pin "4") (pinfunction "ADJ_4") (pintype "input"))
      (node (ref "R32") (pin "1") (pinfunction "1_1") (pintype "passive"))
      (node (ref "R38") (pin "2") (pinfunction "2_2") (pintype "passive"))
    )
    (net (code "24") (name "Net-(IC15A-IN-)") (class "Default")
      (node (ref "IC15") (pin "2") (pinfunction "IN-_2") (pintype "input"))
      (node (ref "R23") (pin "1") (pinfunction "1_1") (pintype "passive"))
    )
    (net (code "25") (name "Net-(IC16-ADJ)") (class "Default")
      (node (ref "IC16") (pin "2") (pinfunction "ADJ_2") (pintype "input"))
      (node (ref "R25") (pin "1") (pinfunction "1_1") (pintype "passive"))
      (node (ref "R29") (pin "2") (pinfunction "2_2") (pintype "passive"))
    )
    (net (code "26") (name "Net-(IC16-BYP)") (class "Default")
      (node (ref "C114") (pin "1") (pinfunction "1_1") (pintype "passive"))
      (node (ref "IC16") (pin "4") (pinfunction "BYP_4") (pintype "passive"))
    )
    (net (code "27") (name "Net-(IC26-FB)") (class "Default")
      (node (ref "IC26") (pin "5") (pinfunction "FB_5") (pintype "input"))
      (node (ref "R20") (pin "1") (pinfunction "1_1") (pintype "passive"))
      (node (ref "R21") (pin "2") (pinfunction "2_2") (pintype "passive"))
    )
    (net (code "28") (name "Net-(IC26-SW)") (class "Default")
      (node (ref "IC26") (pin "9") (pinfunction "SW_9") (pintype "output"))
      (node (ref "L5") (pin "1") (pinfunction "1_1") (pintype "passive"))
    )
    (net (code "29") (name "Net-(IC26-VIN)") (class "Default")
      (node (ref "C122") (pin "2") (pinfunction "2_2") (pintype "passive"))
      (node (ref "C123") (pin "2") (pinfunction "2_2") (pintype "passive"))
      (node (ref "C32") (pin "2") (pinfunction "2_2") (pintype "passive"))
      (node (ref "C34") (pin "2") (pinfunction "2_2") (pintype "passive"))
      (node (ref "C36") (pin "2") (pinfunction "2_2") (pintype "passive"))
      (node (ref "C39") (pin "2") (pinfunction "2_2") (pintype "passive"))
      (node (ref "C49") (pin "1") (pinfunction "1_1") (pintype "passive"))
      (node (ref "C63") (pin "2") (pinfunction "2_2") (pintype "passive"))
      (node (ref "C64") (pin "2") (pinfunction "2_2") (pintype "passive"))
      (node (ref "IC26") (pin "2") (pinfunction "VIN_2") (pintype "input"))
      (node (ref "IC3") (pin "1") (pinfunction "+Vin_1") (pintype "power_in"))
      (node (ref "IC8") (pin "2") (pinfunction "VIN_2") (pintype "input"))
      (node (ref "IC8") (pin "3") (pinfunction "EN_3") (pintype "input"))
      (node (ref "L6") (pin "2") (pinfunction "2_2") (pintype "passive"))
    )
    (net (code "30") (name "P2V5A") (class "Default")
      (node (ref "C47") (pin "2") (pinfunction "2_2") (pintype "passive"))
      (node (ref "C55") (pin "2") (pinfunction "2_2") (pintype "passive"))
      (node (ref "C56") (pin "1") (pinfunction "1_1") (pintype "passive"))
      (node (ref "IC7") (pin "5") (pinfunction "OUT_5") (pintype "power_in"))
      (node (ref "R53") (pin "2") (pinfunction "2_2") (pintype "passive"))
      (node (ref "TP10") (pin "1") (pinfunction "1_1") (pintype "bidirectional"))
    )
    (net (code "31") (name "P3V3") (class "Default")
      (node (ref "C120") (pin "2") (pinfunction "2_2") (pintype "passive"))
      (node (ref "C121") (pin "2") (pinfunction "2_2") (pintype "passive"))
      (node (ref "D5") (pin "1") (pinfunction "C_1") (pintype "passive"))
      (node (ref "IC15") (pin "5") (pinfunction "IN+_5") (pintype "input"))
      (node (ref "IC26") (pin "10") (pinfunction "VOS_10") (pintype "input"))
      (node (ref "IC26") (pin "8") (pinfunction "SLEEP_8") (pintype "input"))
      (node (ref "L1") (pin "1") (pinfunction "1_1") (pintype "passive"))
      (node (ref "L5") (pin "2") (pinfunction "2_2") (pintype "passive"))
      (node (ref "R20") (pin "2") (pinfunction "2_2") (pintype "passive"))
      (node (ref "R51") (pin "1") (pinfunction "1_1") (pintype "passive"))
    )
    (net (code "32") (name "P3V3A") (class "Default")
      (node (ref "C50") (pin "1") (pinfunction "1_1") (pintype "passive"))
      (node (ref "C53") (pin "2") (pinfunction "2_2") (pintype "passive"))
      (node (ref "D2") (pin "1") (pinfunction "C_1") (pintype "passive"))
      (node (ref "IC7") (pin "1") (pinfunction "IN_1") (pintype "input"))
      (node (ref "L1") (pin "2") (pinfunction "2_2") (pintype "passive"))
      (node (ref "R23") (pin "2") (pinfunction "2_2") (pintype "passive"))
      (node (ref "TP11") (pin "1") (pinfunction "1_1") (pintype "bidirectional"))
    )
    (net (code "33") (name "P5V0A") (class "Default")
      (node (ref "C114") (pin "2") (pinfunction "2_2") (pintype "passive"))
      (node (ref "C115") (pin "1") (pinfunction "1_1") (pintype "passive"))
      (node (ref "C62") (pin "2") (pinfunction "2_2") (pintype "passive"))
      (node (ref "IC16") (pin "1") (pinfunction "OUT_1") (pintype "power_in"))
      (node (ref "R25") (pin "2") (pinfunction "2_2") (pintype "passive"))
      (node (ref "TP13") (pin "1") (pinfunction "1_1") (pintype "bidirectional"))
    )
    (net (code "34") (name "P6V0") (class "Default")
      (node (ref "C58") (pin "2") (pinfunction "2_2") (pintype "passive"))
      (node (ref "C59") (pin "2") (pinfunction "2_2") (pintype "passive"))
      (node (ref "IC8") (pin "10") (pinfunction "VOS_10") (pintype "input"))
      (node (ref "IC8") (pin "8") (pinfunction "SLEEP_8") (pintype "input"))
      (node (ref "L3") (pin "2") (pinfunction "2_2") (pintype "passive"))
      (node (ref "L4") (pin "1") (pinfunction "1_1") (pintype "passive"))
      (node (ref "R24") (pin "2") (pinfunction "2_2") (pintype "passive"))
      (node (ref "R57") (pin "2") (pinfunction "2_2") (pintype "passive"))
    )
    (net (code "35") (name "P6V0A") (class "Default")
      (node (ref "C60") (pin "1") (pinfunction "1_1") (pintype "passive"))
      (node (ref "C61") (pin "2") (pinfunction "2_2") (pintype "passive"))
      (node (ref "D4") (pin "1") (pinfunction "C_1") (pintype "passive"))
      (node (ref "IC16") (pin "5") (pinfunction "~{SHDN}_5") (pintype "input"))
      (node (ref "IC16") (pin "8") (pinfunction "IN_8") (pintype "input"))
      (node (ref "L4") (pin "2") (pinfunction "2_2") (pintype "passive"))
      (node (ref "R18") (pin "2") (pinfunction "2_2") (pintype "passive"))
      (node (ref "R56") (pin "2") (pinfunction "2_2") (pintype "passive"))
      (node (ref "TP12") (pin "1") (pinfunction "1_1") (pintype "bidirectional"))
    )
    (net (code "36") (name "P12V0") (class "Default")
      (node (ref "C48") (pin "2") (pinfunction "2_2") (pintype "passive"))
      (node (ref "IC15") (pin "8") (pinfunction "V+_8") (pintype "power_in"))
      (node (ref "L6") (pin "1") (pinfunction "1_1") (pintype "passive"))
    )
    (net (code "37") (name "P12V0A") (class "Default")
      (node (ref "C30") (pin "2") (pinfunction "2_2") (pintype "passive"))
      (node (ref "C51") (pin "1") (pinfunction "1_1") (pintype "passive"))
      (node (ref "C65") (pin "2") (pinfunction "2_2") (pintype "passive"))
      (node (ref "D8") (pin "1") (pinfunction "C_1") (pintype "passive"))
      (node (ref "IC13") (pin "1") (pinfunction "OUT_1") (pintype "power_in"))
      (node (ref "R142") (pin "2") (pinfunction "2_2") (pintype "passive"))
      (node (ref "TP7") (pin "1") (pinfunction "1_1") (pintype "bidirectional"))
    )
    (net (code "38") (name "P13V0") (class "Default")
      (node (ref "C112") (pin "2") (pinfunction "2_2") (pintype "passive"))
      (node (ref "C117") (pin "2") (pinfunction "2_2") (pintype "passive"))
      (node (ref "C29") (pin "2") (pinfunction "2_2") (pintype "passive"))
      (node (ref "C77") (pin "1") (pinfunction "1_1") (pintype "passive"))
      (node (ref "IC13") (pin "8") (pinfunction "IN_8") (pintype "input"))
      (node (ref "IC4") (pin "1") (pinfunction "IN_1") (pintype "input"))
      (node (ref "L11") (pin "2") (pinfunction "2_2") (pintype "passive"))
    )
    (net (code "39") (name "P13V0S") (class "Default")
      (node (ref "C26") (pin "2") (pinfunction "2_2") (pintype "passive"))
      (node (ref "IC3") (pin "7") (pinfunction "+Vout_7") (pintype "power_in"))
      (node (ref "L10") (pin "1") (pinfunction "1_1") (pintype "passive"))
      (node (ref "R7") (pin "2") (pinfunction "2_2") (pintype "passive"))
    )
    (net (code "40") (name "REF_P4V096") (class "Default")
      (node (ref "R22") (pin "1") (pinfunction "1_1") (pintype "passive"))
    )
    (net (code "41") (name "REF_VCC") (class "Default")
      (node (ref "C116") (pin "2") (pinfunction "2_2") (pintype "passive"))
      (node (ref "C118") (pin "1") (pinfunction "1_1") (pintype "passive"))
      (node (ref "C45") (pin "2") (pinfunction "2_2") (pintype "passive"))
      (node (ref "IC4") (pin "5") (pinfunction "OUT_5") (pintype "power_in"))
      (node (ref "R26") (pin "2") (pinfunction "2_2") (pintype "passive"))
      (node (ref "TP8") (pin "1") (pinfunction "1_1") (pintype "bidirectional"))
    )
    (net (code "42") (name "unconnected-(IC8-NC-Pad4)") (class "Default")
      (node (ref "IC8") (pin "4") (pinfunction "NC_4") (pintype "passive"))
    )
    (net (code "43") (name "unconnected-(IC26-NC-Pad4)") (class "Default")
      (node (ref "IC26") (pin "4") (pinfunction "NC_4") (pintype "passive"))
    )
  )
)
